# telem.net
KiCad netlist of a schematic drawn in Altium Designer
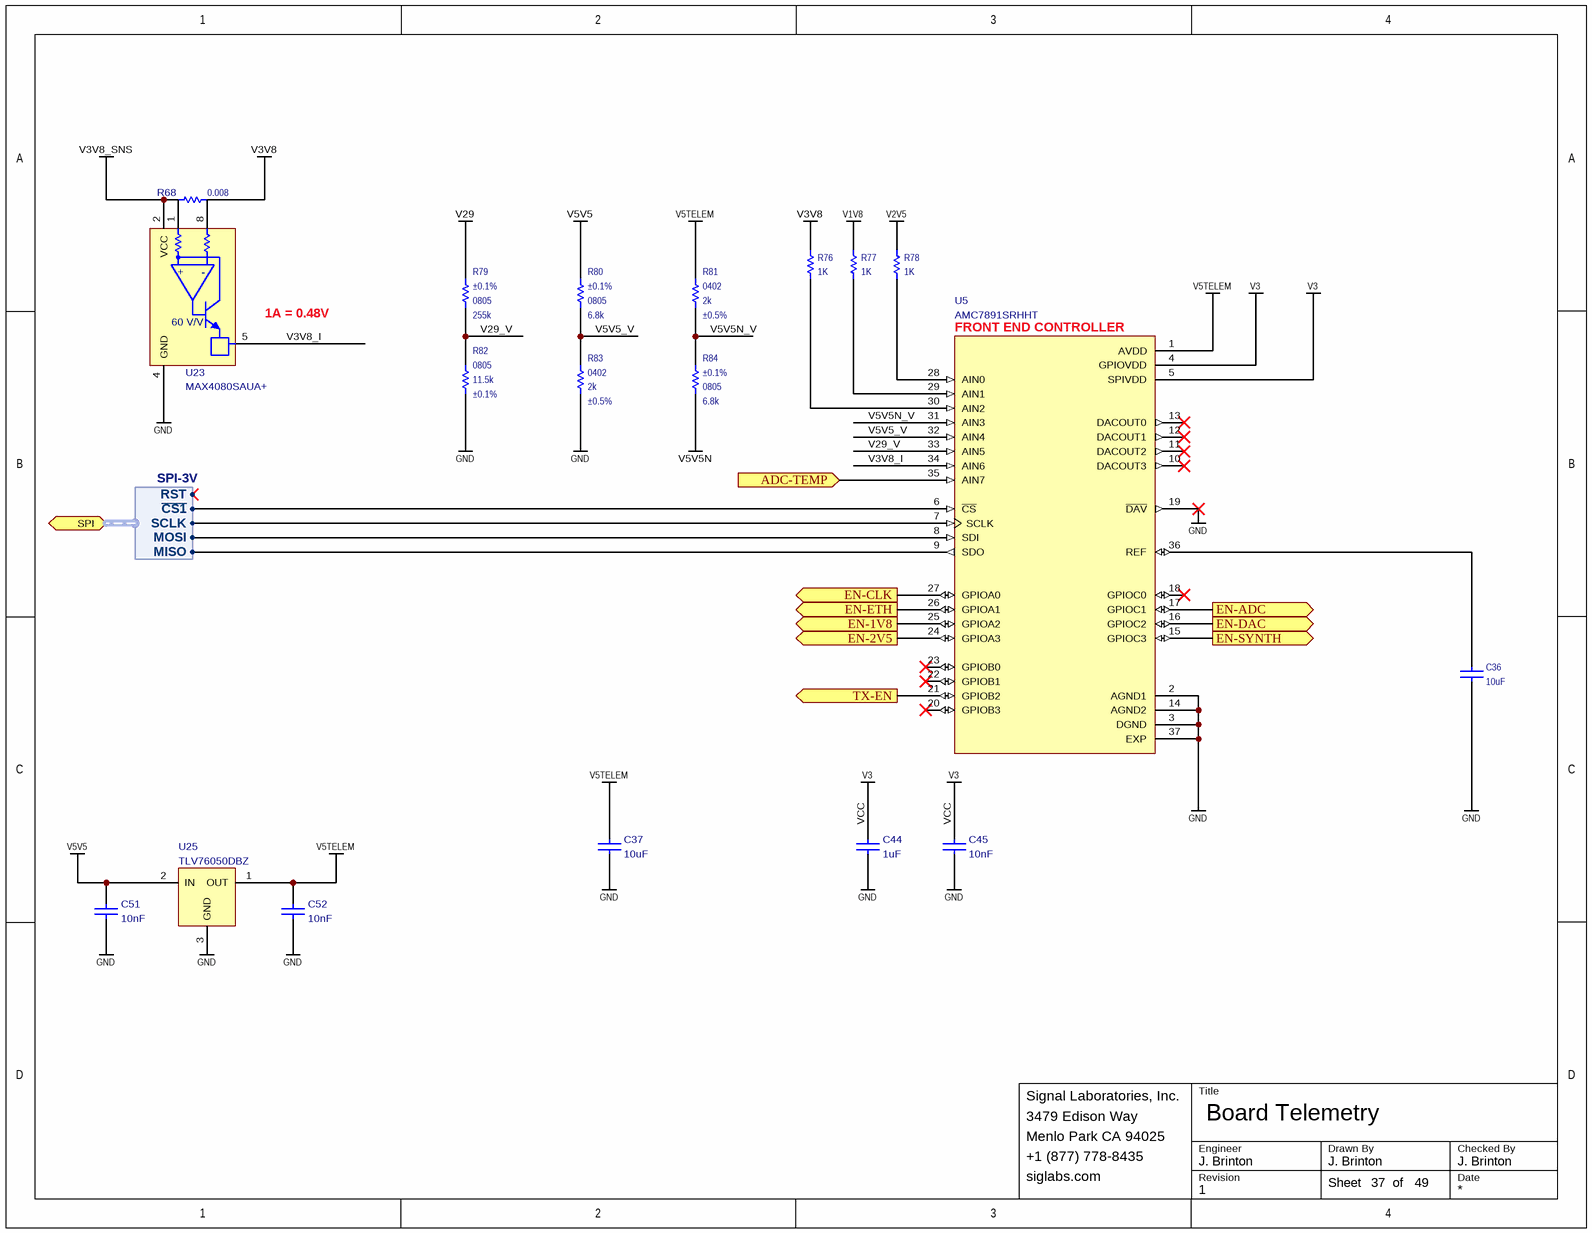
[diagram p0: telem.SchDoc]

(export (version "E")
  (design (tool "Eeschema 10.0.6"))
  (components
    (comp (ref "C36")
      (value "10uF")
      (footprint "CAPC160X80X90L20N")
      (description "Ceramic Capacitor 10uF ±20% 25V X5R 0603")
      (fields (field (name "MANUFACTURER") "Murata") (field (name "TOLERANCE") "±20%"))
      (libsource (lib "generic") (part "CAP"))
    )
    (comp (ref "C37")
      (value "10uF")
      (footprint "CAPC200X125X145L45N")
      (description "Ceramic Capacitor 10uF ±10% 16V X7R 0805")
      (fields (field (name "MANUFACTURER") "Samsung") (field (name "TOLERANCE") "±10%"))
      (libsource (lib "capacitors") (part "CAP"))
    )
    (comp (ref "C44")
      (value "1uF")
      (footprint "CAPC200X125X145L45N")
      (description "Ceramic Capacitor 1uF ±10% 25V X7R 0805")
      (fields (field (name "MANUFACTURER") "Taiyo Yuden") (field (name "TOLERANCE") "±10%"))
      (libsource (lib "capacitors") (part "CAP"))
    )
    (comp (ref "C45")
      (value "10nF")
      (footprint "CAPC100X50X55L25N")
      (description "Ceramic Capacitor 10nF ±10% 50V X7R 0402")
      (fields (field (name "MANUFACTURER") "Murata") (field (name "TOLERANCE") "±10%"))
      (libsource (lib "capacitors") (part "CAP"))
    )
    (comp (ref "C51")
      (value "10nF")
      (footprint "CAPC100X50X55L25N")
      (description "Ceramic Capacitor 10nF ±10% 50V X7R 0402")
      (fields (field (name "MANUFACTURER") "Murata") (field (name "TOLERANCE") "±10%"))
      (libsource (lib "capacitors") (part "CAP"))
    )
    (comp (ref "C52")
      (value "10nF")
      (footprint "CAPC100X50X55L25N")
      (description "Ceramic Capacitor 10nF ±10% 50V X7R 0402")
      (fields (field (name "MANUFACTURER") "Murata") (field (name "TOLERANCE") "±10%"))
      (libsource (lib "capacitors") (part "CAP"))
    )
    (comp (ref "R68")
      (value "0.008")
      (footprint "susumu:KRL3216T4")
      (description "Current Sense Resistor 8 mOhms +/-1% SMD 4-Terminal")
      (fields (field (name "TOLERANCE") "±1%") (field (name "MANUFACTURER") "Susumu"))
      (libsource (lib "susumu") (part "KRL3216T4A-M-R009-F"))
    )
    (comp (ref "R76")
      (value "1K")
      (footprint "RESC1005X40N")
      (description "Thick Film Resistor 1k ±1% 0402")
      (fields (field (name "MANUFACTURER") "Yageo") (field (name "TOLERANCE") "±1%"))
      (libsource (lib "Graviton") (part "RES 0402"))
    )
    (comp (ref "R77")
      (value "1K")
      (footprint "RESC1005X40N")
      (description "Thick Film Resistor 1k ±1% 0402")
      (fields (field (name "MANUFACTURER") "Yageo") (field (name "TOLERANCE") "±1%"))
      (libsource (lib "Graviton") (part "RES 0402"))
    )
    (comp (ref "R78")
      (value "1K")
      (footprint "RESC1005X40N")
      (description "Thick Film Resistor 1k ±1% 0402")
      (fields (field (name "MANUFACTURER") "Yageo") (field (name "TOLERANCE") "±1%"))
      (libsource (lib "Graviton") (part "RES 0402"))
    )
    (comp (ref "R79")
      (value "255k")
      (footprint "RESC2012X70N")
      (description "Thin Film Resistor 255k +/-0.1% SMD 0805")
      (fields
        (field (name "TOLERANCE") "±0.1%")
        (field (name "MANUFACTURER") "Vishay")
        (field (name "PACKAGE") "0805")
        (field (name "Comment") "PTN0805E2553BST1")
      )
      (libsource (lib "generic") (part "RES"))
    )
    (comp (ref "R80")
      (value "6.8k")
      (footprint "RESC2012X70N")
      (description "Thin Film Resistor 6.8k +/-0.1% SMD 0805")
      (fields
        (field (name "TOLERANCE") "±0.1%")
        (field (name "MANUFACTURER") "Susumu")
        (field (name "PACKAGE") "0805")
        (field (name "Comment") "RG2012P-682-B-T5")
      )
      (libsource (lib "generic") (part "RES"))
    )
    (comp (ref "R81")
      (value "2k")
      (footprint "RESC1005X40N")
      (description "Thin Film Resistor 2k +/-0.5% SMD 0402")
      (fields
        (field (name "TOLERANCE") "±0.5%")
        (field (name "MANUFACTURER") "Susumu")
        (field (name "PACKAGE") "0402")
        (field (name "Comment") "RR0510P-202-D")
      )
      (libsource (lib "generic") (part "RES"))
    )
    (comp (ref "R82")
      (value "11.5k")
      (footprint "RESC2012X70N")
      (description "Thin Film Resistor 11.5k +/-0.1% SMD 0805")
      (fields
        (field (name "TOLERANCE") "±0.1%")
        (field (name "MANUFACTURER") "Yageo")
        (field (name "PACKAGE") "0805")
        (field (name "Comment") "RT0805BRD0711K5L")
      )
      (libsource (lib "generic") (part "RES"))
    )
    (comp (ref "R83")
      (value "2k")
      (footprint "RESC1005X40N")
      (description "Thin Film Resistor 2k +/-0.5% SMD 0402")
      (fields
        (field (name "TOLERANCE") "±0.5%")
        (field (name "MANUFACTURER") "Susumu")
        (field (name "PACKAGE") "0402")
        (field (name "Comment") "RR0510P-202-D")
      )
      (libsource (lib "generic") (part "RES"))
    )
    (comp (ref "R84")
      (value "6.8k")
      (footprint "RESC2012X70N")
      (description "Thin Film Resistor 6.8k +/-0.1% SMD 0805")
      (fields
        (field (name "TOLERANCE") "±0.1%")
        (field (name "MANUFACTURER") "Susumu")
        (field (name "PACKAGE") "0805")
        (field (name "Comment") "RG2012P-682-B-T5")
      )
      (libsource (lib "generic") (part "RES"))
    )
    (comp (ref "U5")
      (value "AMC7891SRHHT")
      (footprint "QFN50P600X600X90-37N")
      (description "Analog Monitoring & Control IC")
      (fields (field (name "MANUFACTURER") "Texas Instruments"))
      (libsource (lib "ti") (part "AMC7891SRHHT"))
    )
    (comp (ref "U23")
      (value "MAX4080SAUA+")
      (footprint "maxim:uMAX8")
      (description "High-Side Current-Sense Amplifier")
      (fields (field (name "MANUFACTURER") "Maxim"))
      (libsource (lib "maxim") (part "MAX4080SAUA+"))
    )
    (comp (ref "U25")
      (value "TLV76050DBZ")
      (footprint "generic:SOT23")
      (description "3.3V Fixed-Output LDO")
      (fields (field (name "MANUFACTURER") "Texas Instruments"))
      (libsource (lib "ti") (part "TLV76033DBZ"))
    )
  )
  (nets
    (net (code "2") (name "/ADC-TEMP") (class "Default")
      (node (ref "U5") (pin "35") (pinfunction "AIN7_35") (pintype "input"))
    )
    (net (code "3") (name "/EN-1V8") (class "Default")
      (node (ref "U5") (pin "25") (pinfunction "GPIOA2_25") (pintype "bidirectional"))
    )
    (net (code "4") (name "/EN-2V5") (class "Default")
      (node (ref "U5") (pin "24") (pinfunction "GPIOA3_24") (pintype "bidirectional"))
    )
    (net (code "5") (name "/EN-ADC") (class "Default")
      (node (ref "U5") (pin "17") (pinfunction "GPIOC1_17") (pintype "bidirectional"))
    )
    (net (code "6") (name "/EN-CLK") (class "Default")
      (node (ref "U5") (pin "27") (pinfunction "GPIOA0_27") (pintype "bidirectional"))
    )
    (net (code "7") (name "/EN-DAC") (class "Default")
      (node (ref "U5") (pin "16") (pinfunction "GPIOC2_16") (pintype "bidirectional"))
    )
    (net (code "8") (name "/EN-ETH") (class "Default")
      (node (ref "U5") (pin "26") (pinfunction "GPIOA1_26") (pintype "bidirectional"))
    )
    (net (code "9") (name "/EN-SYNTH") (class "Default")
      (node (ref "U5") (pin "15") (pinfunction "GPIOC3_15") (pintype "bidirectional"))
    )
    (net (code "10") (name "/MISO") (class "Default")
      (node (ref "U5") (pin "9") (pinfunction "SDO_9") (pintype "output"))
    )
    (net (code "11") (name "/MOSI") (class "Default")
      (node (ref "U5") (pin "8") (pinfunction "SDI_8") (pintype "input"))
    )
    (net (code "12") (name "/SCLK") (class "Default")
      (node (ref "U5") (pin "7") (pinfunction "SCLK_7") (pintype "input"))
    )
    (net (code "13") (name "/TX-EN") (class "Default")
      (node (ref "U5") (pin "21") (pinfunction "GPIOB2_21") (pintype "bidirectional"))
    )
    (net (code "14") (name "/V3V8_I") (class "Default")
      (node (ref "U23") (pin "5") (pinfunction "OUT_5") (pintype "passive"))
      (node (ref "U5") (pin "34") (pinfunction "AIN6_34") (pintype "input"))
    )
    (net (code "15") (name "/V5V5N_V") (class "Default")
      (node (ref "R81") (pin "1") (pinfunction "1_1") (pintype "passive"))
      (node (ref "R84") (pin "1") (pinfunction "1_1") (pintype "passive"))
      (node (ref "U5") (pin "31") (pinfunction "AIN3_31") (pintype "input"))
    )
    (net (code "16") (name "/V5V5_V") (class "Default")
      (node (ref "R80") (pin "2") (pinfunction "2_2") (pintype "passive"))
      (node (ref "R83") (pin "2") (pinfunction "2_2") (pintype "passive"))
      (node (ref "U5") (pin "32") (pinfunction "AIN4_32") (pintype "input"))
    )
    (net (code "17") (name "/V29_V") (class "Default")
      (node (ref "R79") (pin "2") (pinfunction "2_2") (pintype "passive"))
      (node (ref "R82") (pin "2") (pinfunction "2_2") (pintype "passive"))
      (node (ref "U5") (pin "33") (pinfunction "AIN5_33") (pintype "input"))
    )
    (net (code "19") (name "/~{CS1}") (class "Default")
      (node (ref "U5") (pin "6") (pinfunction "~{CS}_6") (pintype "input"))
    )
    (net (code "20") (name "GND") (class "Default")
      (node (ref "C36") (pin "1") (pinfunction "1_1") (pintype "passive"))
      (node (ref "C37") (pin "2") (pinfunction "2_2") (pintype "passive"))
      (node (ref "C44") (pin "2") (pinfunction "2_2") (pintype "passive"))
      (node (ref "C45") (pin "2") (pinfunction "2_2") (pintype "passive"))
      (node (ref "C51") (pin "2") (pinfunction "2_2") (pintype "passive"))
      (node (ref "C52") (pin "2") (pinfunction "2_2") (pintype "passive"))
      (node (ref "R82") (pin "1") (pinfunction "1_1") (pintype "passive"))
      (node (ref "R83") (pin "1") (pinfunction "1_1") (pintype "passive"))
      (node (ref "U23") (pin "4") (pinfunction "GND_4") (pintype "passive"))
      (node (ref "U25") (pin "3") (pinfunction "GND_3") (pintype "passive"))
      (node (ref "U5") (pin "14") (pinfunction "AGND2_14") (pintype "power_in"))
      (node (ref "U5") (pin "19") (pinfunction "~{DAV}_19") (pintype "output"))
      (node (ref "U5") (pin "2") (pinfunction "AGND1_2") (pintype "power_in"))
      (node (ref "U5") (pin "3") (pinfunction "DGND_3") (pintype "power_in"))
      (node (ref "U5") (pin "37") (pinfunction "EXP_37") (pintype "power_in"))
    )
    (net (code "21") (name "Net-(U5-AIN0)") (class "Default")
      (node (ref "R78") (pin "1") (pinfunction "1_1") (pintype "passive"))
      (node (ref "U5") (pin "28") (pinfunction "AIN0_28") (pintype "input"))
    )
    (net (code "22") (name "Net-(U5-AIN1)") (class "Default")
      (node (ref "R77") (pin "1") (pinfunction "1_1") (pintype "passive"))
      (node (ref "U5") (pin "29") (pinfunction "AIN1_29") (pintype "input"))
    )
    (net (code "23") (name "Net-(U5-AIN2)") (class "Default")
      (node (ref "R76") (pin "1") (pinfunction "1_1") (pintype "passive"))
      (node (ref "U5") (pin "30") (pinfunction "AIN2_30") (pintype "input"))
    )
    (net (code "24") (name "Net-(U5-REF)") (class "Default")
      (node (ref "C36") (pin "2") (pinfunction "2_2") (pintype "passive"))
      (node (ref "U5") (pin "36") (pinfunction "REF_36") (pintype "bidirectional"))
    )
    (net (code "25") (name "Net-(U23-RS+)") (class "Default")
      (node (ref "R68") (pin "4") (pinfunction "4_4") (pintype "passive"))
      (node (ref "U23") (pin "1") (pinfunction "RS+_1") (pintype "passive"))
    )
    (net (code "26") (name "Net-(U23-RS-)") (class "Default")
      (node (ref "R68") (pin "3") (pinfunction "3_3") (pintype "passive"))
      (node (ref "U23") (pin "8") (pinfunction "RS-_8") (pintype "passive"))
    )
    (net (code "27") (name "V1V8") (class "Default")
      (node (ref "R77") (pin "2") (pinfunction "2_2") (pintype "passive"))
    )
    (net (code "28") (name "V2V5") (class "Default")
      (node (ref "R78") (pin "2") (pinfunction "2_2") (pintype "passive"))
    )
    (net (code "29") (name "V3") (class "Default")
      (node (ref "C44") (pin "1") (pinfunction "1_1") (pintype "passive"))
      (node (ref "C45") (pin "1") (pinfunction "1_1") (pintype "passive"))
      (node (ref "U5") (pin "4") (pinfunction "GPIOVDD_4") (pintype "power_in"))
      (node (ref "U5") (pin "5") (pinfunction "SPIVDD_5") (pintype "power_in"))
    )
    (net (code "30") (name "V3V8") (class "Default")
      (node (ref "R68") (pin "1") (pinfunction "1_1") (pintype "passive"))
      (node (ref "R76") (pin "2") (pinfunction "2_2") (pintype "passive"))
    )
    (net (code "31") (name "V3V8_SNS") (class "Default")
      (node (ref "R68") (pin "2") (pinfunction "2_2") (pintype "passive"))
      (node (ref "U23") (pin "2") (pinfunction "VCC_2") (pintype "passive"))
    )
    (net (code "32") (name "V5TELEM") (class "Default")
      (node (ref "C37") (pin "1") (pinfunction "1_1") (pintype "passive"))
      (node (ref "C52") (pin "1") (pinfunction "1_1") (pintype "passive"))
      (node (ref "R81") (pin "2") (pinfunction "2_2") (pintype "passive"))
      (node (ref "U25") (pin "1") (pinfunction "OUT_1") (pintype "passive"))
      (node (ref "U5") (pin "1") (pinfunction "AVDD_1") (pintype "power_in"))
    )
    (net (code "33") (name "V5V5") (class "Default")
      (node (ref "C51") (pin "1") (pinfunction "1_1") (pintype "passive"))
      (node (ref "R80") (pin "1") (pinfunction "1_1") (pintype "passive"))
      (node (ref "U25") (pin "2") (pinfunction "IN_2") (pintype "passive"))
    )
    (net (code "34") (name "V5V5N") (class "Default")
      (node (ref "R84") (pin "2") (pinfunction "2_2") (pintype "passive"))
    )
    (net (code "35") (name "V29") (class "Default")
      (node (ref "R79") (pin "1") (pinfunction "1_1") (pintype "passive"))
    )
    (net (code "36") (name "unconnected-(U5-DACOUT0-Pad13)") (class "Default")
      (node (ref "U5") (pin "13") (pinfunction "DACOUT0_13") (pintype "output+no_connect"))
    )
    (net (code "37") (name "unconnected-(U5-DACOUT1-Pad12)") (class "Default")
      (node (ref "U5") (pin "12") (pinfunction "DACOUT1_12") (pintype "output+no_connect"))
    )
    (net (code "38") (name "unconnected-(U5-DACOUT2-Pad11)") (class "Default")
      (node (ref "U5") (pin "11") (pinfunction "DACOUT2_11") (pintype "output+no_connect"))
    )
    (net (code "39") (name "unconnected-(U5-DACOUT3-Pad10)") (class "Default")
      (node (ref "U5") (pin "10") (pinfunction "DACOUT3_10") (pintype "output+no_connect"))
    )
    (net (code "40") (name "unconnected-(U5-GPIOB0-Pad23)") (class "Default")
      (node (ref "U5") (pin "23") (pinfunction "GPIOB0_23") (pintype "bidirectional+no_connect"))
    )
    (net (code "41") (name "unconnected-(U5-GPIOB1-Pad22)") (class "Default")
      (node (ref "U5") (pin "22") (pinfunction "GPIOB1_22") (pintype "bidirectional+no_connect"))
    )
    (net (code "42") (name "unconnected-(U5-GPIOB3-Pad20)") (class "Default")
      (node (ref "U5") (pin "20") (pinfunction "GPIOB3_20") (pintype "bidirectional+no_connect"))
    )
    (net (code "43") (name "unconnected-(U5-GPIOC0-Pad18)") (class "Default")
      (node (ref "U5") (pin "18") (pinfunction "GPIOC0_18") (pintype "bidirectional+no_connect"))
    )
  )
)
